# Reaccion-vRegvC.net
KiCad netlist of a schematic drawn in EAGLE
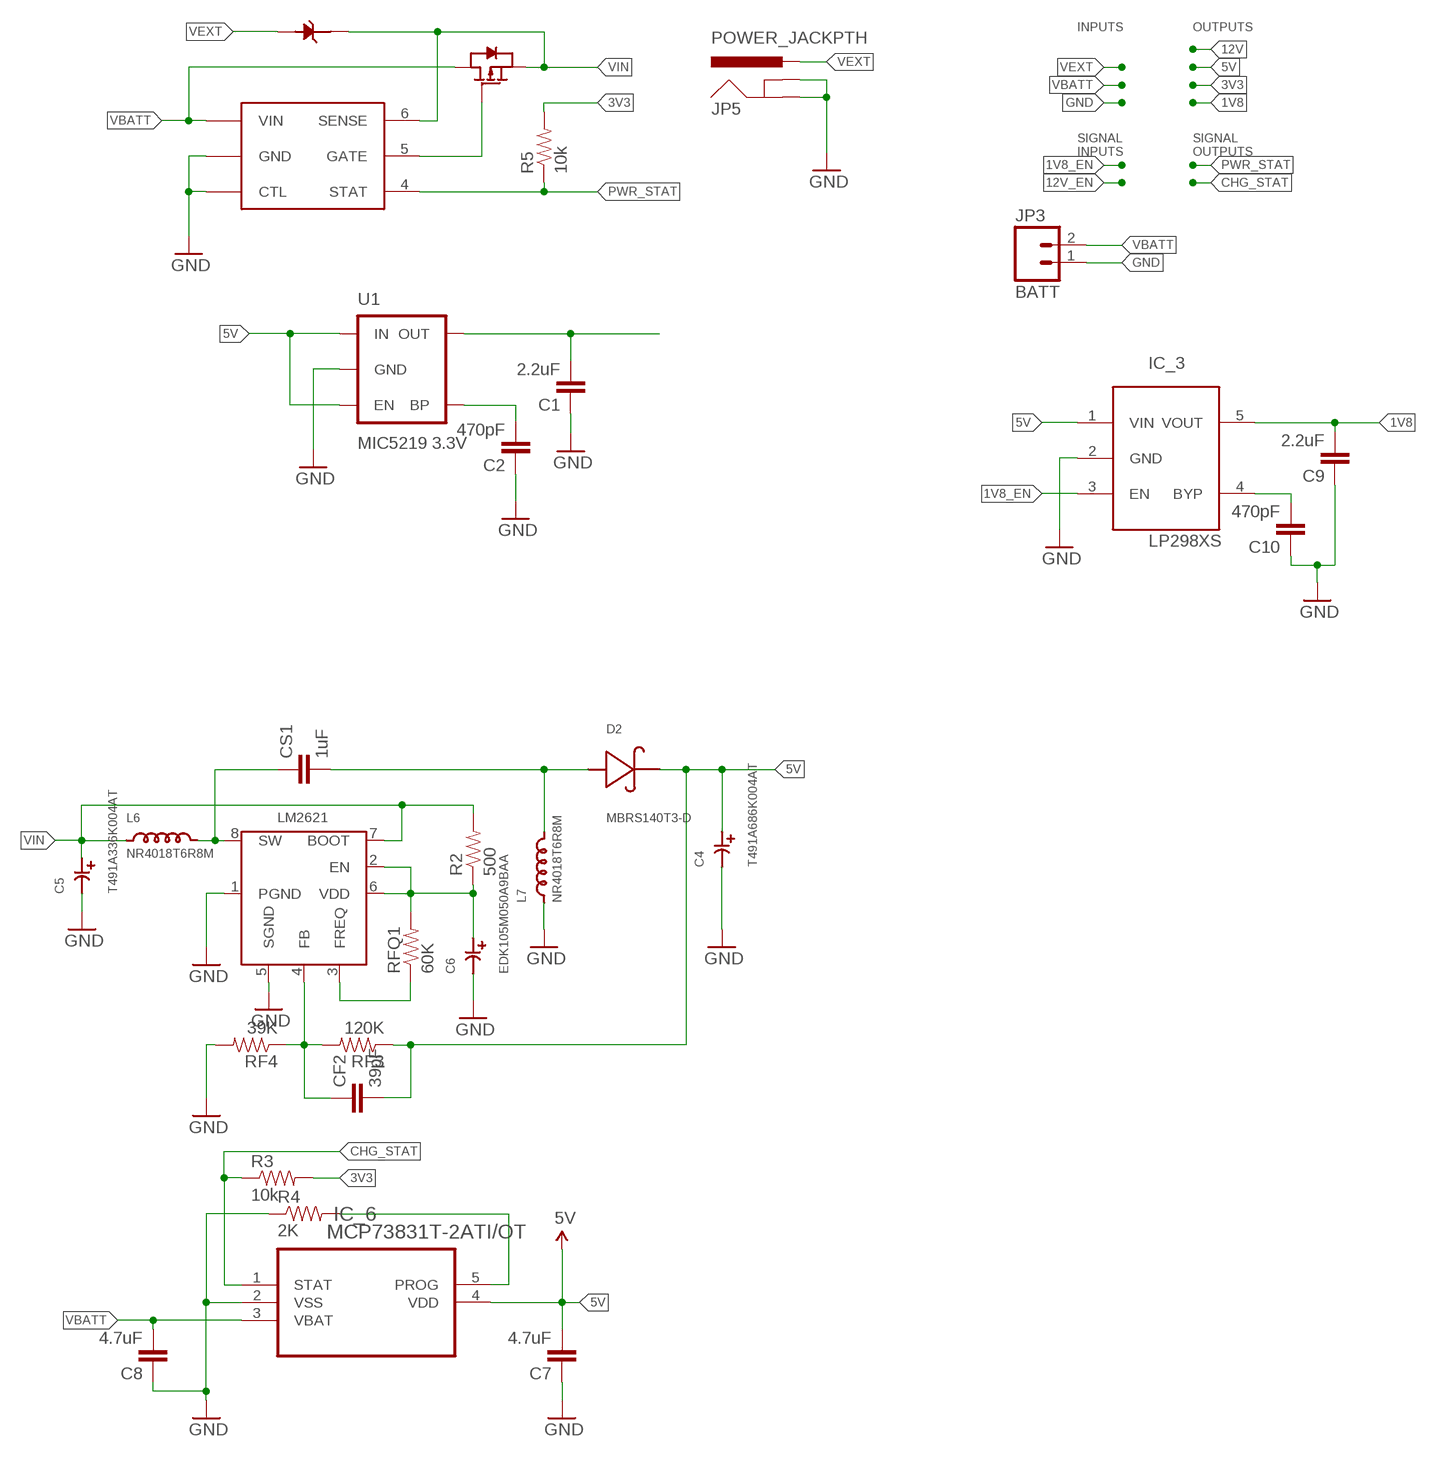
[diagram p0: schematic, sheet 1]

(export (version "E")
  (design (tool "Eeschema 10.0.6"))
  (components
    (comp (ref "C1")
      (value "2.2uF")
      (footprint "eagle-import:0805")
      (libsource (lib "eagle-import") (part "CAP0805"))
    )
    (comp (ref "C2")
      (value "470pF")
      (footprint "eagle-import:0805")
      (libsource (lib "eagle-import") (part "CAP0805"))
    )
    (comp (ref "C4")
      (value "T491A686K004AT")
      (footprint "eagle-import:3216-18")
      (libsource (lib "eagle-import") (part "T491A686K004AT"))
    )
    (comp (ref "C5")
      (value "T491A336K004AT")
      (footprint "eagle-import:3216-18")
      (libsource (lib "eagle-import") (part "T491A336K004AT"))
    )
    (comp (ref "C6")
      (value "EDK105M050A9BAA")
      (footprint "eagle-import:EDK105M050A9BAA")
      (libsource (lib "eagle-import") (part "EDK105M050A9BAA"))
    )
    (comp (ref "C7")
      (value "4.7uF")
      (footprint "eagle-import:0805")
      (libsource (lib "eagle-import") (part "CAP0805"))
    )
    (comp (ref "C8")
      (value "4.7uF")
      (footprint "eagle-import:0805")
      (libsource (lib "eagle-import") (part "CAP0805"))
    )
    (comp (ref "C9")
      (value "2.2uF")
      (footprint "eagle-import:0805")
      (libsource (lib "eagle-import") (part "CAP0805"))
    )
    (comp (ref "C10")
      (value "470pF")
      (footprint "eagle-import:0805")
      (libsource (lib "eagle-import") (part "CAP0805"))
    )
    (comp (ref "CF2")
      (value "39pF")
      (footprint "eagle-import:0805")
      (libsource (lib "eagle-import") (part "CAP0805"))
    )
    (comp (ref "CS1")
      (value "1uF")
      (footprint "eagle-import:0805")
      (libsource (lib "eagle-import") (part "CAP0805"))
    )
    (comp (ref "D2")
      (value "MBRS140T3-D")
      (footprint "eagle-import:MBRS140T3G")
      (libsource (lib "eagle-import") (part "MBRS140T3-D"))
    )
    (comp (ref "D4")
      (value "1N5819HW-7-F")
      (footprint "eagle-import:SOD123")
      (libsource (lib "eagle-import") (part "1N5819HW-7-F"))
    )
    (comp (ref "IC_1")
      (value "LTC4412")
      (footprint "eagle-import:SOT23-6L")
      (libsource (lib "eagle-import") (part "LTC4412"))
    )
    (comp (ref "IC_3")
      (value "LP298XS")
      (footprint "eagle-import:SOT23-5L")
      (libsource (lib "eagle-import") (part "LP298XS"))
    )
    (comp (ref "IC_4")
      (value "LM2621")
      (footprint "eagle-import:R-PDSO-G8")
      (libsource (lib "eagle-import") (part "LM2621"))
    )
    (comp (ref "IC_6")
      (value "MCP73831T-2ATI/OT")
      (footprint "eagle-import:SOT95P300X145-5N")
      (libsource (lib "eagle-import") (part "MCP73831T-2ATI/OT"))
    )
    (comp (ref "JP3")
      (value "BATT")
      (footprint "eagle-import:JST-2-PTH-NS")
      (libsource (lib "eagle-import") (part "M02-JST-2-PTH-NO_SILK"))
    )
    (comp (ref "JP5")
      (value "POWER_JACKPTH")
      (footprint "eagle-import:POWER_JACK_PTH")
      (libsource (lib "eagle-import") (part "POWER_JACKPTH"))
    )
    (comp (ref "L6")
      (value "NR4018T6R8M")
      (footprint "eagle-import:NR4018_NRS4018")
      (libsource (lib "eagle-import") (part "NR4018T6R8M"))
    )
    (comp (ref "L7")
      (value "NR4018T6R8M")
      (footprint "eagle-import:NR4018_NRS4018")
      (libsource (lib "eagle-import") (part "NR4018T6R8M"))
    )
    (comp (ref "Q9")
      (value "SI2301CDS")
      (footprint "eagle-import:SOT23")
      (libsource (lib "eagle-import") (part "SI2301CDS"))
    )
    (comp (ref "R2")
      (value "500")
      (footprint "eagle-import:0805")
      (libsource (lib "eagle-import") (part "RESISTOR0805-RES"))
    )
    (comp (ref "R3")
      (value "10k")
      (footprint "eagle-import:0805")
      (libsource (lib "eagle-import") (part "RESISTOR0805-RES"))
    )
    (comp (ref "R4")
      (value "2K")
      (footprint "eagle-import:0805")
      (libsource (lib "eagle-import") (part "RESISTOR0805-RES"))
    )
    (comp (ref "R5")
      (value "10k")
      (footprint "eagle-import:0805")
      (libsource (lib "eagle-import") (part "RESISTOR0805-RES"))
    )
    (comp (ref "RF3")
      (value "120K")
      (footprint "eagle-import:0805")
      (libsource (lib "eagle-import") (part "RESISTOR0805-RES"))
    )
    (comp (ref "RF4")
      (value "39K")
      (footprint "eagle-import:0805")
      (libsource (lib "eagle-import") (part "RESISTOR0805-RES"))
    )
    (comp (ref "RFQ1")
      (value "60K")
      (footprint "eagle-import:0805")
      (libsource (lib "eagle-import") (part "RESISTOR0805-RES"))
    )
    (comp (ref "U1")
      (value "MIC5219 3.3V")
      (footprint "eagle-import:SOT23-5")
      (libsource (lib "eagle-import") (part "V_REG_MIC52193.3V"))
    )
  )
  (nets
    (net (code "1") (name "1V8") (class "Default")
      (node (ref "C9") (pin "2") (pinfunction "2_2") (pintype "passive"))
      (node (ref "IC_3") (pin "5") (pinfunction "VOUT_5") (pintype "bidirectional"))
    )
    (net (code "2") (name "1V8_EN") (class "Default")
      (node (ref "IC_3") (pin "3") (pinfunction "EN_3") (pintype "bidirectional"))
    )
    (net (code "3") (name "3V3") (class "Default")
      (node (ref "C1") (pin "2") (pinfunction "2_2") (pintype "passive"))
      (node (ref "R3") (pin "2") (pinfunction "2_2") (pintype "passive"))
      (node (ref "R5") (pin "2") (pinfunction "2_2") (pintype "passive"))
      (node (ref "U1") (pin "5") (pinfunction "OUT_5") (pintype "passive"))
    )
    (net (code "4") (name "5V") (class "Default")
      (node (ref "C4") (pin "1") (pinfunction "P$1_1") (pintype "bidirectional"))
      (node (ref "C7") (pin "2") (pinfunction "2_2") (pintype "passive"))
      (node (ref "CF2") (pin "2") (pinfunction "2_2") (pintype "passive"))
      (node (ref "D2") (pin "2") (pinfunction "2_2") (pintype "bidirectional"))
      (node (ref "IC_3") (pin "1") (pinfunction "VIN_1") (pintype "bidirectional"))
      (node (ref "IC_6") (pin "4") (pinfunction "VDD_4") (pintype "power_in"))
      (node (ref "RF3") (pin "1") (pinfunction "1_1") (pintype "passive"))
      (node (ref "U1") (pin "1") (pinfunction "IN_1") (pintype "input"))
      (node (ref "U1") (pin "3") (pinfunction "EN_3") (pintype "input"))
    )
    (net (code "7") (name "CHG_STAT") (class "Default")
      (node (ref "IC_6") (pin "1") (pinfunction "STAT_1") (pintype "input"))
      (node (ref "R3") (pin "1") (pinfunction "1_1") (pintype "passive"))
    )
    (net (code "8") (name "GND") (class "Default")
      (node (ref "C1") (pin "1") (pinfunction "1_1") (pintype "passive"))
      (node (ref "C10") (pin "1") (pinfunction "1_1") (pintype "passive"))
      (node (ref "C2") (pin "1") (pinfunction "1_1") (pintype "passive"))
      (node (ref "C4") (pin "2") (pinfunction "P$2_2") (pintype "bidirectional"))
      (node (ref "C5") (pin "2") (pinfunction "P$2_2") (pintype "bidirectional"))
      (node (ref "C6") (pin "P$2") (pinfunction "P$2_P$2") (pintype "bidirectional"))
      (node (ref "C7") (pin "1") (pinfunction "1_1") (pintype "passive"))
      (node (ref "C8") (pin "1") (pinfunction "1_1") (pintype "passive"))
      (node (ref "C9") (pin "1") (pinfunction "1_1") (pintype "passive"))
      (node (ref "IC_1") (pin "2") (pinfunction "GND_2") (pintype "power_in"))
      (node (ref "IC_1") (pin "3") (pinfunction "CTL_3") (pintype "input"))
      (node (ref "IC_3") (pin "2") (pinfunction "GND_2") (pintype "bidirectional"))
      (node (ref "IC_4") (pin "1") (pinfunction "PGND_1") (pintype "bidirectional"))
      (node (ref "IC_4") (pin "5") (pinfunction "SGND_5") (pintype "bidirectional"))
      (node (ref "IC_6") (pin "2") (pinfunction "VSS_2") (pintype "passive"))
      (node (ref "JP3") (pin "1") (pinfunction "1_1") (pintype "passive"))
      (node (ref "JP5") (pin "GND") (pinfunction "GND_GND") (pintype "bidirectional"))
      (node (ref "JP5") (pin "GNDBREAK") (pinfunction "GNDBREAK_GNDBREAK") (pintype "bidirectional"))
      (node (ref "L7") (pin "P$1") (pinfunction "P$1_P$1") (pintype "bidirectional"))
      (node (ref "R4") (pin "1") (pinfunction "1_1") (pintype "passive"))
      (node (ref "RF4") (pin "2") (pinfunction "2_2") (pintype "passive"))
      (node (ref "U1") (pin "2") (pinfunction "GND_2") (pintype "input"))
    )
    (net (code "9") (name "Net-(CS1-Pad2)") (class "Default")
      (node (ref "CS1") (pin "2") (pinfunction "2_2") (pintype "passive"))
      (node (ref "D2") (pin "1") (pinfunction "1_1") (pintype "bidirectional"))
      (node (ref "L7") (pin "P$2") (pinfunction "P$2_P$2") (pintype "bidirectional"))
    )
    (net (code "10") (name "Net-(IC_1-GATE)") (class "Default")
      (node (ref "IC_1") (pin "5") (pinfunction "GATE_5") (pintype "output"))
      (node (ref "Q9") (pin "1") (pinfunction "GATE_1") (pintype "passive"))
    )
    (net (code "11") (name "Net-(IC_3-BYP)") (class "Default")
      (node (ref "C10") (pin "2") (pinfunction "2_2") (pintype "passive"))
      (node (ref "IC_3") (pin "4") (pinfunction "BYP_4") (pintype "bidirectional"))
    )
    (net (code "12") (name "Net-(IC_4-EN)") (class "Default")
      (node (ref "C6") (pin "P$1") (pinfunction "P$1_P$1") (pintype "bidirectional"))
      (node (ref "IC_4") (pin "2") (pinfunction "EN_2") (pintype "bidirectional"))
      (node (ref "IC_4") (pin "6") (pinfunction "VDD_6") (pintype "bidirectional"))
      (node (ref "R2") (pin "1") (pinfunction "1_1") (pintype "passive"))
      (node (ref "RFQ1") (pin "2") (pinfunction "2_2") (pintype "passive"))
    )
    (net (code "13") (name "Net-(IC_4-FB)") (class "Default")
      (node (ref "CF2") (pin "1") (pinfunction "1_1") (pintype "passive"))
      (node (ref "IC_4") (pin "4") (pinfunction "FB_4") (pintype "bidirectional"))
      (node (ref "RF3") (pin "2") (pinfunction "2_2") (pintype "passive"))
      (node (ref "RF4") (pin "1") (pinfunction "1_1") (pintype "passive"))
    )
    (net (code "14") (name "Net-(IC_4-FREQ)") (class "Default")
      (node (ref "IC_4") (pin "3") (pinfunction "FREQ_3") (pintype "bidirectional"))
      (node (ref "RFQ1") (pin "1") (pinfunction "1_1") (pintype "passive"))
    )
    (net (code "15") (name "Net-(IC_4-SW)") (class "Default")
      (node (ref "CS1") (pin "1") (pinfunction "1_1") (pintype "passive"))
      (node (ref "IC_4") (pin "8") (pinfunction "SW_8") (pintype "bidirectional"))
      (node (ref "L6") (pin "P$2") (pinfunction "P$2_P$2") (pintype "bidirectional"))
    )
    (net (code "16") (name "Net-(IC_6-PROG)") (class "Default")
      (node (ref "IC_6") (pin "5") (pinfunction "PROG_5") (pintype "input"))
      (node (ref "R4") (pin "2") (pinfunction "2_2") (pintype "passive"))
    )
    (net (code "17") (name "Net-(U1-BP)") (class "Default")
      (node (ref "C2") (pin "2") (pinfunction "2_2") (pintype "passive"))
      (node (ref "U1") (pin "4") (pinfunction "BP_4") (pintype "input"))
    )
    (net (code "18") (name "PWR_STAT") (class "Default")
      (node (ref "IC_1") (pin "4") (pinfunction "STAT_4") (pintype "output"))
      (node (ref "R5") (pin "1") (pinfunction "1_1") (pintype "passive"))
    )
    (net (code "19") (name "VBATT") (class "Default")
      (node (ref "C8") (pin "2") (pinfunction "2_2") (pintype "passive"))
      (node (ref "IC_1") (pin "1") (pinfunction "VIN_1") (pintype "power_in"))
      (node (ref "IC_6") (pin "3") (pinfunction "VBAT_3") (pintype "input"))
      (node (ref "JP3") (pin "2") (pinfunction "2_2") (pintype "passive"))
      (node (ref "Q9") (pin "3") (pinfunction "DRAIN_3") (pintype "passive"))
    )
    (net (code "20") (name "VEXT") (class "Default")
      (node (ref "D4") (pin "2") (pinfunction "ANODE_2") (pintype "passive"))
      (node (ref "JP5") (pin "PWR") (pinfunction "PWR_PWR") (pintype "bidirectional"))
    )
    (net (code "21") (name "VIN") (class "Default")
      (node (ref "C5") (pin "1") (pinfunction "P$1_1") (pintype "bidirectional"))
      (node (ref "D4") (pin "1") (pinfunction "CATHODE_1") (pintype "passive"))
      (node (ref "IC_1") (pin "6") (pinfunction "SENSE_6") (pintype "input"))
      (node (ref "IC_4") (pin "7") (pinfunction "BOOT_7") (pintype "bidirectional"))
      (node (ref "L6") (pin "P$1") (pinfunction "P$1_P$1") (pintype "bidirectional"))
      (node (ref "Q9") (pin "2") (pinfunction "SOURCE_2") (pintype "passive"))
      (node (ref "R2") (pin "2") (pinfunction "2_2") (pintype "passive"))
    )
  )
)
